# AT24-Timer.net
KiCad netlist of a schematic drawn in EAGLE
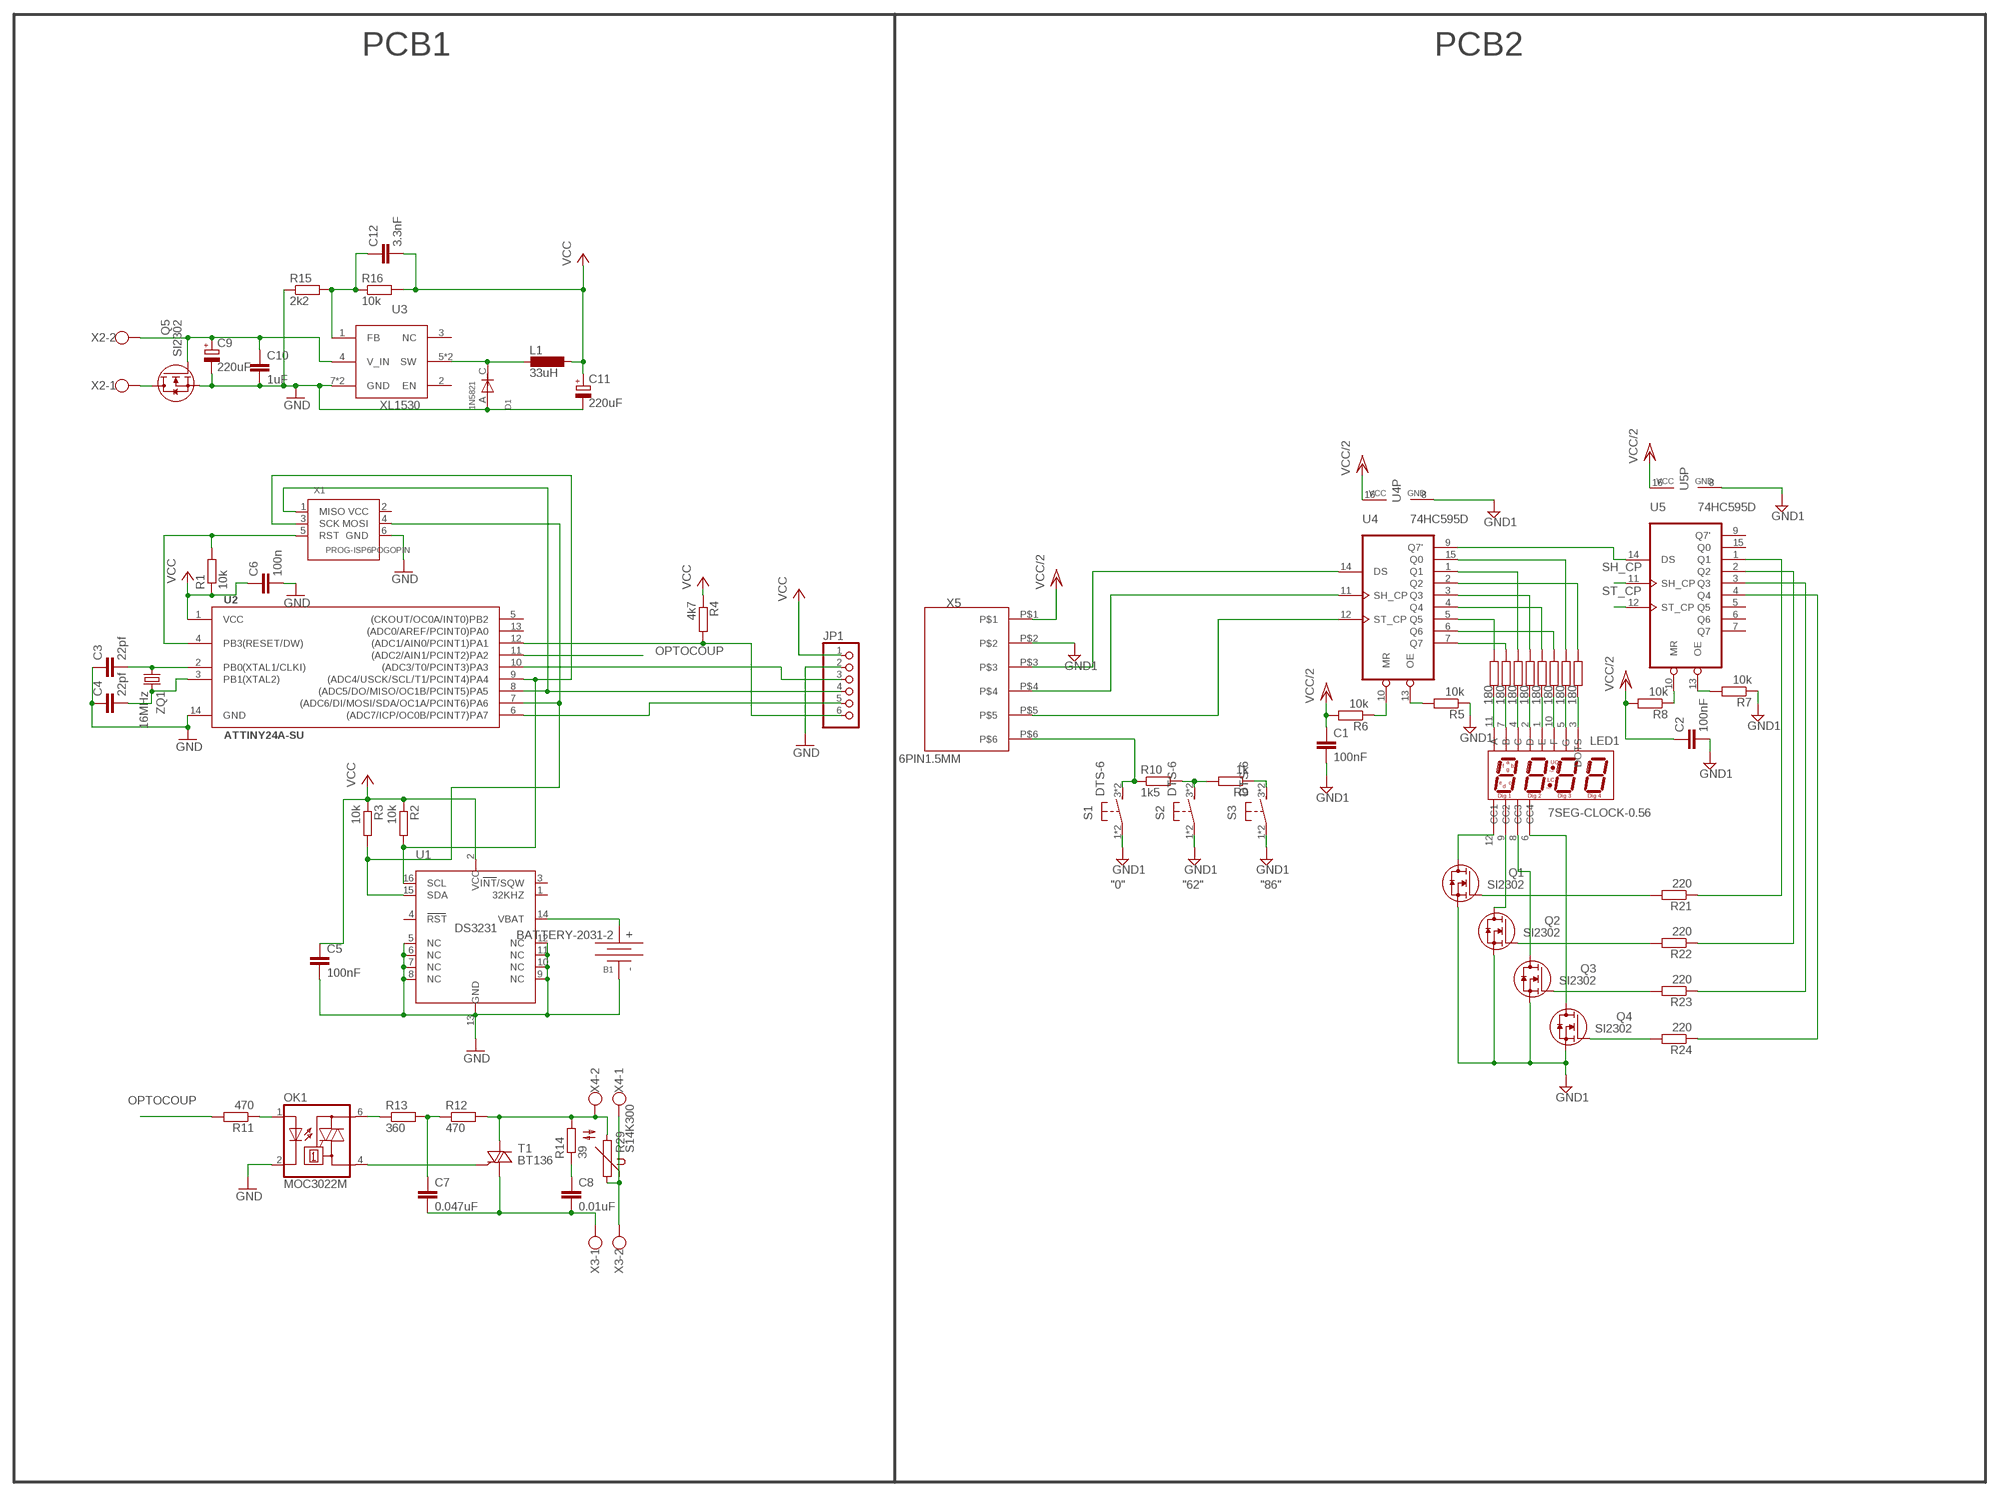
[diagram p0: schematic, sheet 1]

(export (version "E")
  (design (tool "Eeschema 10.0.6"))
  (components
    (comp (ref "B1")
      (value "BATTERY-2031-2")
      (footprint "eagle-import:BTH2032-2")
      (libsource (lib "eagle-import") (part "BATTERY-2031-2"))
    )
    (comp (ref "C1")
      (value "100nF")
      (footprint "eagle-import:C0603")
      (libsource (lib "eagle-import") (part "C-EUC0603"))
    )
    (comp (ref "C2")
      (value "100nF")
      (footprint "eagle-import:C0603")
      (libsource (lib "eagle-import") (part "C-EUC0603"))
    )
    (comp (ref "C3")
      (value "22pf")
      (footprint "eagle-import:C0603")
      (libsource (lib "eagle-import") (part "C-EUC0603"))
    )
    (comp (ref "C4")
      (value "22pf")
      (footprint "eagle-import:C0603")
      (libsource (lib "eagle-import") (part "C-EUC0603"))
    )
    (comp (ref "C5")
      (value "100nF")
      (footprint "eagle-import:C0603")
      (libsource (lib "eagle-import") (part "C-EUC0603"))
    )
    (comp (ref "C6")
      (value "100n")
      (footprint "eagle-import:C0603")
      (libsource (lib "eagle-import") (part "C-EUC0603"))
    )
    (comp (ref "C7")
      (value "0.047uF")
      (footprint "eagle-import:C150-054X183")
      (libsource (lib "eagle-import") (part "C-EU150-054X183"))
    )
    (comp (ref "C8")
      (value "0.01uF")
      (footprint "eagle-import:C102-043X133")
      (libsource (lib "eagle-import") (part "C-EU102-043X133"))
    )
    (comp (ref "C9")
      (value "220uF")
      (footprint "eagle-import:E2,5-6E")
      (libsource (lib "eagle-import") (part "CPOL-EUE2,5-6E"))
    )
    (comp (ref "C10")
      (value "1uF")
      (footprint "eagle-import:C0805")
      (libsource (lib "eagle-import") (part "C-EUC0805"))
    )
    (comp (ref "C11")
      (value "220uF")
      (footprint "eagle-import:E2,5-6E")
      (libsource (lib "eagle-import") (part "CPOL-EUE2,5-6E"))
    )
    (comp (ref "C12")
      (value "3.3nF")
      (footprint "eagle-import:C0805")
      (libsource (lib "eagle-import") (part "C-EUC0805"))
    )
    (comp (ref "D1")
      (value "1N5821")
      (footprint "eagle-import:DO214AC")
      (libsource (lib "eagle-import") (part "DIODESMD"))
    )
    (comp (ref "JP1")
      (value "PINHD-1X6")
      (footprint "eagle-import:1X06")
      (libsource (lib "eagle-import") (part "PINHD-1X6"))
    )
    (comp (ref "L1")
      (value "33uH")
      (footprint "eagle-import:L-SMD-D10")
      (libsource (lib "eagle-import") (part "L-SMD"))
    )
    (comp (ref "LED1")
      (value "7SEG-CLOCK-0.56")
      (footprint "eagle-import:7SEG_4DIG_0.56")
      (libsource (lib "eagle-import") (part "7SEG-CLOCK-0.56"))
    )
    (comp (ref "OK1")
      (value "MOC3022M")
      (footprint "eagle-import:DIL06")
      (fields (field (name "MF") "FAIRCHILD SEMICONDUCTOR") (field (name "MPN") "MOC3022-M"))
      (libsource (lib "eagle-import") (part "MOC30M22"))
    )
    (comp (ref "Q1")
      (value "SI2302")
      (footprint "eagle-import:SOT-23-GSD")
      (libsource (lib "eagle-import") (part "SI2302"))
    )
    (comp (ref "Q2")
      (value "SI2302")
      (footprint "eagle-import:SOT-23-GSD")
      (libsource (lib "eagle-import") (part "SI2302"))
    )
    (comp (ref "Q3")
      (value "SI2302")
      (footprint "eagle-import:SOT-23-GSD")
      (libsource (lib "eagle-import") (part "SI2302"))
    )
    (comp (ref "Q4")
      (value "SI2302")
      (footprint "eagle-import:SOT-23-GSD")
      (libsource (lib "eagle-import") (part "SI2302"))
    )
    (comp (ref "Q5")
      (value "SI2302")
      (footprint "eagle-import:SOT-23-GSD")
      (libsource (lib "eagle-import") (part "SI2302"))
    )
    (comp (ref "R1")
      (value "10k")
      (footprint "eagle-import:R0805")
      (libsource (lib "eagle-import") (part "R-EU_R0805"))
    )
    (comp (ref "R2")
      (value "10k")
      (footprint "eagle-import:R0805")
      (libsource (lib "eagle-import") (part "R-EU_R0805"))
    )
    (comp (ref "R3")
      (value "10k")
      (footprint "eagle-import:R0805")
      (libsource (lib "eagle-import") (part "R-EU_R0805"))
    )
    (comp (ref "R4")
      (value "4k7")
      (footprint "eagle-import:R0805")
      (libsource (lib "eagle-import") (part "R-EU_R0805"))
    )
    (comp (ref "R5")
      (value "10k")
      (footprint "eagle-import:R0805")
      (libsource (lib "eagle-import") (part "R-EU_R0805"))
    )
    (comp (ref "R6")
      (value "10k")
      (footprint "eagle-import:R0805")
      (libsource (lib "eagle-import") (part "R-EU_R0805"))
    )
    (comp (ref "R7")
      (value "10k")
      (footprint "eagle-import:R0805")
      (libsource (lib "eagle-import") (part "R-EU_R0805"))
    )
    (comp (ref "R8")
      (value "10k")
      (footprint "eagle-import:R0805")
      (libsource (lib "eagle-import") (part "R-EU_R0805"))
    )
    (comp (ref "R9")
      (value "1k")
      (footprint "eagle-import:R0805")
      (libsource (lib "eagle-import") (part "R-EU_R0805"))
    )
    (comp (ref "R10")
      (value "1k5")
      (footprint "eagle-import:R0805")
      (libsource (lib "eagle-import") (part "R-EU_R0805"))
    )
    (comp (ref "R11")
      (value "470")
      (footprint "eagle-import:R0805")
      (libsource (lib "eagle-import") (part "R-EU_R0805"))
    )
    (comp (ref "R12")
      (value "470")
      (footprint "eagle-import:0207_7")
      (libsource (lib "eagle-import") (part "R-EU_0207/7"))
    )
    (comp (ref "R13")
      (value "360")
      (footprint "eagle-import:0207_7")
      (libsource (lib "eagle-import") (part "R-EU_0207/7"))
    )
    (comp (ref "R14")
      (value "39")
      (footprint "eagle-import:0207_7")
      (libsource (lib "eagle-import") (part "R-EU_0207/7"))
    )
    (comp (ref "R15")
      (value "2k2")
      (footprint "eagle-import:R0603")
      (libsource (lib "eagle-import") (part "R-EU_R0603"))
    )
    (comp (ref "R16")
      (value "10k")
      (footprint "eagle-import:R0603")
      (libsource (lib "eagle-import") (part "R-EU_R0603"))
    )
    (comp (ref "R17")
      (value "180")
      (footprint "eagle-import:R0805")
      (libsource (lib "eagle-import") (part "R-EU_R0805"))
    )
    (comp (ref "R18")
      (value "180")
      (footprint "eagle-import:R0805")
      (libsource (lib "eagle-import") (part "R-EU_R0805"))
    )
    (comp (ref "R19")
      (value "180")
      (footprint "eagle-import:R0805")
      (libsource (lib "eagle-import") (part "R-EU_R0805"))
    )
    (comp (ref "R20")
      (value "180")
      (footprint "eagle-import:R0805")
      (libsource (lib "eagle-import") (part "R-EU_R0805"))
    )
    (comp (ref "R21")
      (value "220")
      (footprint "eagle-import:R0805")
      (libsource (lib "eagle-import") (part "R-EU_R0805"))
    )
    (comp (ref "R22")
      (value "220")
      (footprint "eagle-import:R0805")
      (libsource (lib "eagle-import") (part "R-EU_R0805"))
    )
    (comp (ref "R23")
      (value "220")
      (footprint "eagle-import:R0805")
      (libsource (lib "eagle-import") (part "R-EU_R0805"))
    )
    (comp (ref "R24")
      (value "220")
      (footprint "eagle-import:R0805")
      (libsource (lib "eagle-import") (part "R-EU_R0805"))
    )
    (comp (ref "R25")
      (value "180")
      (footprint "eagle-import:R0805")
      (libsource (lib "eagle-import") (part "R-EU_R0805"))
    )
    (comp (ref "R26")
      (value "180")
      (footprint "eagle-import:R0805")
      (libsource (lib "eagle-import") (part "R-EU_R0805"))
    )
    (comp (ref "R27")
      (value "180")
      (footprint "eagle-import:R0805")
      (libsource (lib "eagle-import") (part "R-EU_R0805"))
    )
    (comp (ref "R28")
      (value "180")
      (footprint "eagle-import:R0805")
      (libsource (lib "eagle-import") (part "R-EU_R0805"))
    )
    (comp (ref "R29")
      (value "S14K300")
      (footprint "eagle-import:S14K300")
      (libsource (lib "eagle-import") (part "S14K300"))
    )
    (comp (ref "S1")
      (value "DTS-6")
      (footprint "eagle-import:DTS-6")
      (libsource (lib "eagle-import") (part "DTS-6"))
    )
    (comp (ref "S2")
      (value "DTS-6")
      (footprint "eagle-import:DTS-6")
      (libsource (lib "eagle-import") (part "DTS-6"))
    )
    (comp (ref "S3")
      (value "DTS-6")
      (footprint "eagle-import:DTS-6")
      (libsource (lib "eagle-import") (part "DTS-6"))
    )
    (comp (ref "T1")
      (value "BT136")
      (footprint "eagle-import:TO220AB")
      (libsource (lib "eagle-import") (part "BT136"))
    )
    (comp (ref "U1")
      (value "DS3231")
      (footprint "eagle-import:SO16L")
      (libsource (lib "eagle-import") (part "DS3231"))
    )
    (comp (ref "U2")
      (value "ATTINY24A-SU")
      (footprint "eagle-import:SO14")
      (libsource (lib "eagle-import") (part "ATTINY24A-SU"))
    )
    (comp (ref "U3")
      (value "XL1530")
      (footprint "eagle-import:SOP08")
      (libsource (lib "eagle-import") (part "XL1530"))
    )
    (comp (ref "U4")
      (value "74HC595D")
      (footprint "eagle-import:SO16")
      (libsource (lib "eagle-import") (part "74595DHC"))
    )
    (comp (ref "U5")
      (value "74HC595D")
      (footprint "eagle-import:SO16")
      (libsource (lib "eagle-import") (part "74595DHC"))
    )
    (comp (ref "X1")
      (value "PROG-ISP6POGOPIN")
      (footprint "eagle-import:PROG_POGOPIN")
      (libsource (lib "eagle-import") (part "PROG-ISP6POGOPIN"))
    )
    (comp (ref "X2")
      (value "W237-102")
      (footprint "eagle-import:W237-102")
      (fields (field (name "MPN") "237-102"))
      (libsource (lib "eagle-import") (part "W237-102"))
    )
    (comp (ref "X3")
      (value "W237-102")
      (footprint "eagle-import:W237-102")
      (fields (field (name "MPN") "237-102"))
      (libsource (lib "eagle-import") (part "W237-102"))
    )
    (comp (ref "X4")
      (value "W237-102")
      (footprint "eagle-import:W237-102")
      (fields (field (name "MPN") "237-102"))
      (libsource (lib "eagle-import") (part "W237-102"))
    )
    (comp (ref "X5")
      (value "6PIN1.5MM")
      (footprint "eagle-import:6PIN_1.5MM")
      (libsource (lib "eagle-import") (part "6PIN1.5MM"))
    )
    (comp (ref "ZQ1")
      (value "16MHz")
      (footprint "eagle-import:HC49_S")
      (libsource (lib "eagle-import") (part "CRYSTALHC49S"))
    )
  )
  (nets
    (net (code "1") (name "/OPTOCOUP") (class "Default")
      (node (ref "R11") (pin "2") (pinfunction "2_2") (pintype "passive"))
      (node (ref "U2") (pin "11") (pinfunction "(ADC2/AIN1/PCINT2)PA2_11") (pintype "bidirectional"))
    )
    (net (code "2") (name "/SH_CP") (class "Default")
      (node (ref "U4") (pin "11") (pinfunction "SH_CP_11") (pintype "input"))
      (node (ref "U5") (pin "11") (pinfunction "SH_CP_11") (pintype "input"))
      (node (ref "X5") (pin "P$4") (pinfunction "P$4_P$4") (pintype "bidirectional"))
    )
    (net (code "3") (name "/ST_CP") (class "Default")
      (node (ref "U4") (pin "12") (pinfunction "ST_CP_12") (pintype "input"))
      (node (ref "U5") (pin "12") (pinfunction "ST_CP_12") (pintype "input"))
      (node (ref "X5") (pin "P$5") (pinfunction "P$5_P$5") (pintype "bidirectional"))
    )
    (net (code "4") (name "GND") (class "Default")
      (node (ref "B1") (pin "-") (pinfunction "-_-") (pintype "power_in"))
      (node (ref "C10") (pin "2") (pinfunction "2_2") (pintype "passive"))
      (node (ref "C11") (pin "-") (pinfunction "-_-") (pintype "passive"))
      (node (ref "C3") (pin "1") (pinfunction "1_1") (pintype "passive"))
      (node (ref "C4") (pin "1") (pinfunction "1_1") (pintype "passive"))
      (node (ref "C5") (pin "2") (pinfunction "2_2") (pintype "passive"))
      (node (ref "C6") (pin "2") (pinfunction "2_2") (pintype "passive"))
      (node (ref "C9") (pin "-") (pinfunction "-_-") (pintype "passive"))
      (node (ref "D1") (pin "A") (pinfunction "ANOD_A") (pintype "power_in"))
      (node (ref "JP1") (pin "2") (pinfunction "2_2") (pintype "passive"))
      (node (ref "OK1") (pin "2") (pinfunction "C_2") (pintype "passive"))
      (node (ref "Q5") (pin "S") (pinfunction "S_S") (pintype "passive"))
      (node (ref "R15") (pin "1") (pinfunction "1_1") (pintype "passive"))
      (node (ref "U1") (pin "10") (pinfunction "NC_10") (pintype "bidirectional"))
      (node (ref "U1") (pin "11") (pinfunction "NC_11") (pintype "bidirectional"))
      (node (ref "U1") (pin "12") (pinfunction "NC_12") (pintype "bidirectional"))
      (node (ref "U1") (pin "13") (pinfunction "GND_13") (pintype "power_in"))
      (node (ref "U1") (pin "5") (pinfunction "NC_5") (pintype "bidirectional"))
      (node (ref "U1") (pin "6") (pinfunction "NC_6") (pintype "bidirectional"))
      (node (ref "U1") (pin "7") (pinfunction "NC_7") (pintype "bidirectional"))
      (node (ref "U1") (pin "8") (pinfunction "NC_8") (pintype "bidirectional"))
      (node (ref "U1") (pin "9") (pinfunction "NC_9") (pintype "bidirectional"))
      (node (ref "U2") (pin "14") (pinfunction "GND_14") (pintype "power_in"))
      (node (ref "U3") (pin "7") (pinfunction "GND_7") (pintype "bidirectional"))
      (node (ref "U3") (pin "8") (pinfunction "GND_8") (pintype "bidirectional"))
      (node (ref "X1") (pin "6") (pinfunction "GND_6") (pintype "power_in"))
    )
    (net (code "5") (name "GND1") (class "Default")
      (node (ref "C1") (pin "2") (pinfunction "2_2") (pintype "passive"))
      (node (ref "C2") (pin "2") (pinfunction "2_2") (pintype "passive"))
      (node (ref "Q1") (pin "S") (pinfunction "S_S") (pintype "passive"))
      (node (ref "Q2") (pin "S") (pinfunction "S_S") (pintype "passive"))
      (node (ref "Q3") (pin "S") (pinfunction "S_S") (pintype "passive"))
      (node (ref "Q4") (pin "S") (pinfunction "S_S") (pintype "passive"))
      (node (ref "R5") (pin "1") (pinfunction "1_1") (pintype "passive"))
      (node (ref "R7") (pin "1") (pinfunction "1_1") (pintype "passive"))
      (node (ref "S1") (pin "1") (pinfunction "1_1") (pintype "passive"))
      (node (ref "S1") (pin "2") (pinfunction "1_2") (pintype "passive"))
      (node (ref "S2") (pin "1") (pinfunction "1_1") (pintype "passive"))
      (node (ref "S2") (pin "2") (pinfunction "1_2") (pintype "passive"))
      (node (ref "S3") (pin "1") (pinfunction "1_1") (pintype "passive"))
      (node (ref "S3") (pin "2") (pinfunction "1_2") (pintype "passive"))
      (node (ref "U4") (pin "8") (pinfunction "GND_8") (pintype "power_in"))
      (node (ref "U5") (pin "8") (pinfunction "GND_8") (pintype "power_in"))
      (node (ref "X5") (pin "P$2") (pinfunction "P$2_P$2") (pintype "bidirectional"))
    )
    (net (code "6") (name "Net-(C7-Pad1)") (class "Default")
      (node (ref "C7") (pin "1") (pinfunction "1_1") (pintype "passive"))
      (node (ref "R12") (pin "1") (pinfunction "1_1") (pintype "passive"))
      (node (ref "R13") (pin "2") (pinfunction "2_2") (pintype "passive"))
    )
    (net (code "7") (name "Net-(C8-Pad1)") (class "Default")
      (node (ref "C8") (pin "1") (pinfunction "1_1") (pintype "passive"))
      (node (ref "R14") (pin "1") (pinfunction "1_1") (pintype "passive"))
    )
    (net (code "8") (name "Net-(D1-KATOD)") (class "Default")
      (node (ref "D1") (pin "C") (pinfunction "KATOD_C") (pintype "power_in"))
      (node (ref "L1") (pin "P$2") (pinfunction "2_P$2") (pintype "passive"))
      (node (ref "U3") (pin "5") (pinfunction "SW_5") (pintype "bidirectional"))
      (node (ref "U3") (pin "6") (pinfunction "SW_6") (pintype "bidirectional"))
    )
    (net (code "9") (name "Net-(LED1-A)") (class "Default")
      (node (ref "LED1") (pin "11") (pinfunction "A_11") (pintype "input"))
      (node (ref "R17") (pin "2") (pinfunction "2_2") (pintype "passive"))
    )
    (net (code "10") (name "Net-(LED1-B)") (class "Default")
      (node (ref "LED1") (pin "7") (pinfunction "B_7") (pintype "input"))
      (node (ref "R18") (pin "2") (pinfunction "2_2") (pintype "passive"))
    )
    (net (code "11") (name "Net-(LED1-C)") (class "Default")
      (node (ref "LED1") (pin "4") (pinfunction "C_4") (pintype "input"))
      (node (ref "R19") (pin "2") (pinfunction "2_2") (pintype "passive"))
    )
    (net (code "12") (name "Net-(LED1-CC1)") (class "Default")
      (node (ref "LED1") (pin "12") (pinfunction "CC1_12") (pintype "input"))
      (node (ref "Q1") (pin "D") (pinfunction "D_D") (pintype "passive"))
    )
    (net (code "13") (name "Net-(LED1-CC2)") (class "Default")
      (node (ref "LED1") (pin "9") (pinfunction "CC2_9") (pintype "input"))
      (node (ref "Q2") (pin "D") (pinfunction "D_D") (pintype "passive"))
    )
    (net (code "14") (name "Net-(LED1-CC3)") (class "Default")
      (node (ref "LED1") (pin "8") (pinfunction "CC3_8") (pintype "input"))
      (node (ref "Q3") (pin "D") (pinfunction "D_D") (pintype "passive"))
    )
    (net (code "15") (name "Net-(LED1-CC4)") (class "Default")
      (node (ref "LED1") (pin "6") (pinfunction "CC4_6") (pintype "input"))
      (node (ref "Q4") (pin "D") (pinfunction "D_D") (pintype "passive"))
    )
    (net (code "16") (name "Net-(LED1-D)") (class "Default")
      (node (ref "LED1") (pin "2") (pinfunction "D_2") (pintype "input"))
      (node (ref "R20") (pin "2") (pinfunction "2_2") (pintype "passive"))
    )
    (net (code "17") (name "Net-(LED1-DOTS)") (class "Default")
      (node (ref "LED1") (pin "3") (pinfunction "DOTS_3") (pintype "input"))
      (node (ref "R28") (pin "2") (pinfunction "2_2") (pintype "passive"))
    )
    (net (code "18") (name "Net-(LED1-E)") (class "Default")
      (node (ref "LED1") (pin "1") (pinfunction "E_1") (pintype "input"))
      (node (ref "R25") (pin "2") (pinfunction "2_2") (pintype "passive"))
    )
    (net (code "19") (name "Net-(LED1-F)") (class "Default")
      (node (ref "LED1") (pin "10") (pinfunction "F_10") (pintype "input"))
      (node (ref "R26") (pin "2") (pinfunction "2_2") (pintype "passive"))
    )
    (net (code "20") (name "Net-(LED1-G)") (class "Default")
      (node (ref "LED1") (pin "5") (pinfunction "G_5") (pintype "input"))
      (node (ref "R27") (pin "2") (pinfunction "2_2") (pintype "passive"))
    )
    (net (code "21") (name "Net-(OK1-A)") (class "Default")
      (node (ref "OK1") (pin "1") (pinfunction "A_1") (pintype "passive"))
      (node (ref "R11") (pin "1") (pinfunction "1_1") (pintype "passive"))
    )
    (net (code "22") (name "Net-(OK1-A1)") (class "Default")
      (node (ref "OK1") (pin "4") (pinfunction "A1_4") (pintype "passive"))
      (node (ref "T1") (pin "3") (pinfunction "G_3") (pintype "passive"))
    )
    (net (code "23") (name "Net-(OK1-A2)") (class "Default")
      (node (ref "OK1") (pin "6") (pinfunction "A2_6") (pintype "passive"))
      (node (ref "R13") (pin "1") (pinfunction "1_1") (pintype "passive"))
    )
    (net (code "24") (name "Net-(Q1-PadG)") (class "Default")
      (node (ref "Q1") (pin "G") (pinfunction "G_G") (pintype "passive"))
      (node (ref "R21") (pin "2") (pinfunction "2_2") (pintype "passive"))
    )
    (net (code "25") (name "Net-(Q2-PadG)") (class "Default")
      (node (ref "Q2") (pin "G") (pinfunction "G_G") (pintype "passive"))
      (node (ref "R22") (pin "2") (pinfunction "2_2") (pintype "passive"))
    )
    (net (code "26") (name "Net-(Q3-PadG)") (class "Default")
      (node (ref "Q3") (pin "G") (pinfunction "G_G") (pintype "passive"))
      (node (ref "R23") (pin "2") (pinfunction "2_2") (pintype "passive"))
    )
    (net (code "27") (name "Net-(Q4-PadG)") (class "Default")
      (node (ref "Q4") (pin "G") (pinfunction "G_G") (pintype "passive"))
      (node (ref "R24") (pin "2") (pinfunction "2_2") (pintype "passive"))
    )
    (net (code "28") (name "Net-(R9-Pad1)") (class "Default")
      (node (ref "R9") (pin "1") (pinfunction "1_1") (pintype "passive"))
      (node (ref "S3") (pin "3") (pinfunction "2_3") (pintype "passive"))
      (node (ref "S3") (pin "4") (pinfunction "2_4") (pintype "passive"))
    )
    (net (code "29") (name "Net-(R10-Pad1)") (class "Default")
      (node (ref "R10") (pin "1") (pinfunction "1_1") (pintype "passive"))
      (node (ref "S1") (pin "3") (pinfunction "2_3") (pintype "passive"))
      (node (ref "S1") (pin "4") (pinfunction "2_4") (pintype "passive"))
      (node (ref "X5") (pin "P$6") (pinfunction "P$6_P$6") (pintype "bidirectional"))
    )
    (net (code "30") (name "Net-(R10-Pad2)") (class "Default")
      (node (ref "R10") (pin "2") (pinfunction "2_2") (pintype "passive"))
      (node (ref "R9") (pin "2") (pinfunction "2_2") (pintype "passive"))
      (node (ref "S2") (pin "3") (pinfunction "2_3") (pintype "passive"))
      (node (ref "S2") (pin "4") (pinfunction "2_4") (pintype "passive"))
    )
    (net (code "31") (name "Net-(T1-A1)") (class "Default")
      (node (ref "C7") (pin "2") (pinfunction "2_2") (pintype "passive"))
      (node (ref "C8") (pin "2") (pinfunction "2_2") (pintype "passive"))
      (node (ref "T1") (pin "1") (pinfunction "A1_1") (pintype "passive"))
      (node (ref "X3") (pin "1") (pinfunction "KL_1") (pintype "passive"))
    )
    (net (code "32") (name "Net-(T1-A2)") (class "Default")
      (node (ref "R12") (pin "2") (pinfunction "2_2") (pintype "passive"))
      (node (ref "R14") (pin "2") (pinfunction "2_2") (pintype "passive"))
      (node (ref "R29") (pin "2") (pinfunction "2_2") (pintype "passive"))
      (node (ref "T1") (pin "2") (pinfunction "A2_2") (pintype "passive"))
      (node (ref "X4") (pin "2") (pinfunction "KL_2") (pintype "passive"))
    )
    (net (code "33") (name "Net-(U1-SCL)") (class "Default")
      (node (ref "R2") (pin "2") (pinfunction "2_2") (pintype "passive"))
      (node (ref "U1") (pin "16") (pinfunction "SCL_16") (pintype "bidirectional"))
      (node (ref "U2") (pin "9") (pinfunction "(ADC4/USCK/SCL/T1/PCINT4)PA4_9") (pintype "bidirectional"))
      (node (ref "X1") (pin "3") (pinfunction "SCK_3") (pintype "bidirectional"))
    )
    (net (code "34") (name "Net-(U1-SDA)") (class "Default")
      (node (ref "R3") (pin "2") (pinfunction "2_2") (pintype "passive"))
      (node (ref "U1") (pin "15") (pinfunction "SDA_15") (pintype "bidirectional"))
      (node (ref "U2") (pin "7") (pinfunction "(ADC6/DI/MOSI/SDA/OC1A/PCINT6)PA6_7") (pintype "bidirectional"))
      (node (ref "X1") (pin "4") (pinfunction "MOSI_4") (pintype "bidirectional"))
    )
    (net (code "35") (name "Net-(U1-VBAT)") (class "Default")
      (node (ref "B1") (pin "+") (pinfunction "+_+") (pintype "power_in"))
      (node (ref "U1") (pin "14") (pinfunction "VBAT_14") (pintype "bidirectional"))
    )
    (net (code "36") (name "Net-(U2-(ADC1{slash}AIN0{slash}PCINT1)PA1)") (class "Default")
      (node (ref "JP1") (pin "6") (pinfunction "6_6") (pintype "passive"))
      (node (ref "R4") (pin "2") (pinfunction "2_2") (pintype "passive"))
      (node (ref "U2") (pin "12") (pinfunction "(ADC1/AIN0/PCINT1)PA1_12") (pintype "bidirectional"))
    )
    (net (code "37") (name "Net-(U2-(ADC3{slash}T0{slash}PCINT3)PA3)") (class "Default")
      (node (ref "JP1") (pin "3") (pinfunction "3_3") (pintype "passive"))
      (node (ref "U2") (pin "10") (pinfunction "(ADC3/T0/PCINT3)PA3_10") (pintype "bidirectional"))
    )
    (net (code "38") (name "Net-(U2-(ADC5{slash}DO{slash}MISO{slash}OC1B{slash}PCINT5)PA5)") (class "Default")
      (node (ref "JP1") (pin "4") (pinfunction "4_4") (pintype "passive"))
      (node (ref "U2") (pin "8") (pinfunction "(ADC5/DO/MISO/OC1B/PCINT5)PA5_8") (pintype "bidirectional"))
      (node (ref "X1") (pin "1") (pinfunction "MISO_1") (pintype "bidirectional"))
    )
    (net (code "39") (name "Net-(U2-(ADC7{slash}ICP{slash}OC0B{slash}PCINT7)PA7)") (class "Default")
      (node (ref "JP1") (pin "5") (pinfunction "5_5") (pintype "passive"))
      (node (ref "U2") (pin "6") (pinfunction "(ADC7/ICP/OC0B/PCINT7)PA7_6") (pintype "bidirectional"))
    )
    (net (code "40") (name "Net-(U2-PB0(XTAL1{slash}CLKI))") (class "Default")
      (node (ref "C3") (pin "2") (pinfunction "2_2") (pintype "passive"))
      (node (ref "U2") (pin "2") (pinfunction "PB0(XTAL1/CLKI)_2") (pintype "bidirectional"))
      (node (ref "ZQ1") (pin "1") (pinfunction "1_1") (pintype "passive"))
    )
    (net (code "41") (name "Net-(U2-PB1(XTAL2))") (class "Default")
      (node (ref "C4") (pin "2") (pinfunction "2_2") (pintype "passive"))
      (node (ref "U2") (pin "3") (pinfunction "PB1(XTAL2)_3") (pintype "bidirectional"))
      (node (ref "ZQ1") (pin "2") (pinfunction "2_2") (pintype "passive"))
    )
    (net (code "42") (name "Net-(U2-PB3(RESET{slash}DW))") (class "Default")
      (node (ref "R1") (pin "2") (pinfunction "2_2") (pintype "passive"))
      (node (ref "U2") (pin "4") (pinfunction "PB3(RESET/DW)_4") (pintype "bidirectional"))
      (node (ref "X1") (pin "5") (pinfunction "RST_5") (pintype "bidirectional"))
    )
    (net (code "43") (name "Net-(U3-FB)") (class "Default")
      (node (ref "C12") (pin "1") (pinfunction "1_1") (pintype "passive"))
      (node (ref "R15") (pin "2") (pinfunction "2_2") (pintype "passive"))
      (node (ref "R16") (pin "1") (pinfunction "1_1") (pintype "passive"))
      (node (ref "U3") (pin "1") (pinfunction "FB_1") (pintype "bidirectional"))
    )
    (net (code "44") (name "Net-(U3-V_IN)") (class "Default")
      (node (ref "C10") (pin "1") (pinfunction "1_1") (pintype "passive"))
      (node (ref "C9") (pin "+") (pinfunction "+_+") (pintype "passive"))
      (node (ref "Q5") (pin "G") (pinfunction "G_G") (pintype "passive"))
      (node (ref "U3") (pin "4") (pinfunction "V_IN_4") (pintype "bidirectional"))
      (node (ref "X2") (pin "2") (pinfunction "KL_2") (pintype "passive"))
    )
    (net (code "45") (name "Net-(U4A-DS)") (class "Default")
      (node (ref "U4") (pin "14") (pinfunction "DS_14") (pintype "input"))
      (node (ref "X5") (pin "P$3") (pinfunction "P$3_P$3") (pintype "bidirectional"))
    )
    (net (code "46") (name "Net-(U4A-MR)") (class "Default")
      (node (ref "R6") (pin "1") (pinfunction "1_1") (pintype "passive"))
      (node (ref "U4") (pin "10") (pinfunction "MR_10") (pintype "input"))
    )
    (net (code "47") (name "Net-(U4A-OE)") (class "Default")
      (node (ref "R5") (pin "2") (pinfunction "2_2") (pintype "passive"))
      (node (ref "U4") (pin "13") (pinfunction "OE_13") (pintype "input"))
    )
    (net (code "48") (name "Net-(U4A-Q0)") (class "Default")
      (node (ref "R27") (pin "1") (pinfunction "1_1") (pintype "passive"))
      (node (ref "U4") (pin "15") (pinfunction "Q0_15") (pintype "output"))
    )
    (net (code "49") (name "Net-(U4A-Q1)") (class "Default")
      (node (ref "R19") (pin "1") (pinfunction "1_1") (pintype "passive"))
      (node (ref "U4") (pin "1") (pinfunction "Q1_1") (pintype "output"))
    )
    (net (code "50") (name "Net-(U4A-Q2)") (class "Default")
      (node (ref "R28") (pin "1") (pinfunction "1_1") (pintype "passive"))
      (node (ref "U4") (pin "2") (pinfunction "Q2_2") (pintype "output"))
    )
    (net (code "51") (name "Net-(U4A-Q3)") (class "Default")
      (node (ref "R20") (pin "1") (pinfunction "1_1") (pintype "passive"))
      (node (ref "U4") (pin "3") (pinfunction "Q3_3") (pintype "output"))
    )
    (net (code "52") (name "Net-(U4A-Q4)") (class "Default")
      (node (ref "R25") (pin "1") (pinfunction "1_1") (pintype "passive"))
      (node (ref "U4") (pin "4") (pinfunction "Q4_4") (pintype "output"))
    )
    (net (code "53") (name "Net-(U4A-Q5)") (class "Default")
      (node (ref "R17") (pin "1") (pinfunction "1_1") (pintype "passive"))
      (node (ref "U4") (pin "5") (pinfunction "Q5_5") (pintype "output"))
    )
    (net (code "54") (name "Net-(U4A-Q6)") (class "Default")
      (node (ref "R26") (pin "1") (pinfunction "1_1") (pintype "passive"))
      (node (ref "U4") (pin "6") (pinfunction "Q6_6") (pintype "output"))
    )
    (net (code "55") (name "Net-(U4A-Q7')") (class "Default")
      (node (ref "U4") (pin "9") (pinfunction "Q7'_9") (pintype "output"))
      (node (ref "U5") (pin "14") (pinfunction "DS_14") (pintype "input"))
    )
    (net (code "56") (name "Net-(U4A-Q7)") (class "Default")
      (node (ref "R18") (pin "1") (pinfunction "1_1") (pintype "passive"))
      (node (ref "U4") (pin "7") (pinfunction "Q7_7") (pintype "output"))
    )
    (net (code "57") (name "Net-(U5A-MR)") (class "Default")
      (node (ref "R8") (pin "1") (pinfunction "1_1") (pintype "passive"))
      (node (ref "U5") (pin "10") (pinfunction "MR_10") (pintype "input"))
    )
    (net (code "58") (name "Net-(U5A-OE)") (class "Default")
      (node (ref "R7") (pin "2") (pinfunction "2_2") (pintype "passive"))
      (node (ref "U5") (pin "13") (pinfunction "OE_13") (pintype "input"))
    )
    (net (code "59") (name "Net-(U5A-Q1)") (class "Default")
      (node (ref "R21") (pin "1") (pinfunction "1_1") (pintype "passive"))
      (node (ref "U5") (pin "1") (pinfunction "Q1_1") (pintype "output"))
    )
    (net (code "60") (name "Net-(U5A-Q2)") (class "Default")
      (node (ref "R22") (pin "1") (pinfunction "1_1") (pintype "passive"))
      (node (ref "U5") (pin "2") (pinfunction "Q2_2") (pintype "output"))
    )
    (net (code "61") (name "Net-(U5A-Q3)") (class "Default")
      (node (ref "R23") (pin "1") (pinfunction "1_1") (pintype "passive"))
      (node (ref "U5") (pin "3") (pinfunction "Q3_3") (pintype "output"))
    )
    (net (code "62") (name "Net-(U5A-Q4)") (class "Default")
      (node (ref "R24") (pin "1") (pinfunction "1_1") (pintype "passive"))
      (node (ref "U5") (pin "4") (pinfunction "Q4_4") (pintype "output"))
    )
    (net (code "63") (name "Net-(X2A-KL)") (class "Default")
      (node (ref "Q5") (pin "D") (pinfunction "D_D") (pintype "passive"))
      (node (ref "X2") (pin "1") (pinfunction "KL_1") (pintype "passive"))
    )
    (net (code "64") (name "Net-(X3B-KL)") (class "Default")
      (node (ref "R29") (pin "1") (pinfunction "1_1") (pintype "passive"))
      (node (ref "X3") (pin "2") (pinfunction "KL_2") (pintype "passive"))
      (node (ref "X4") (pin "1") (pinfunction "KL_1") (pintype "passive"))
    )
    (net (code "65") (name "VCC") (class "Default")
      (node (ref "C11") (pin "+") (pinfunction "+_+") (pintype "passive"))
      (node (ref "C12") (pin "2") (pinfunction "2_2") (pintype "passive"))
      (node (ref "C5") (pin "1") (pinfunction "1_1") (pintype "passive"))
      (node (ref "C6") (pin "1") (pinfunction "1_1") (pintype "passive"))
      (node (ref "JP1") (pin "1") (pinfunction "1_1") (pintype "passive"))
      (node (ref "L1") (pin "P$1") (pinfunction "1_P$1") (pintype "passive"))
      (node (ref "R1") (pin "1") (pinfunction "1_1") (pintype "passive"))
      (node (ref "R16") (pin "2") (pinfunction "2_2") (pintype "passive"))
      (node (ref "R2") (pin "1") (pinfunction "1_1") (pintype "passive"))
      (node (ref "R3") (pin "1") (pinfunction "1_1") (pintype "passive"))
      (node (ref "R4") (pin "1") (pinfunction "1_1") (pintype "passive"))
      (node (ref "U1") (pin "2") (pinfunction "VCC_2") (pintype "power_in"))
      (node (ref "U2") (pin "1") (pinfunction "VCC_1") (pintype "power_in"))
    )
    (net (code "66") (name "VCC{slash}2") (class "Default")
      (node (ref "C1") (pin "1") (pinfunction "1_1") (pintype "passive"))
      (node (ref "C2") (pin "1") (pinfunction "1_1") (pintype "passive"))
      (node (ref "R6") (pin "2") (pinfunction "2_2") (pintype "passive"))
      (node (ref "R8") (pin "2") (pinfunction "2_2") (pintype "passive"))
      (node (ref "U4") (pin "16") (pinfunction "VCC_16") (pintype "power_in"))
      (node (ref "U5") (pin "16") (pinfunction "VCC_16") (pintype "power_in"))
      (node (ref "X5") (pin "P$1") (pinfunction "P$1_P$1") (pintype "bidirectional"))
    )
    (net (code "67") (name "unconnected-(U1-32KHZ-Pad1)") (class "Default")
      (node (ref "U1") (pin "1") (pinfunction "32KHZ_1") (pintype "bidirectional"))
    )
    (net (code "68") (name "unconnected-(U1-INT{slash}SQW-Pad3)") (class "Default")
      (node (ref "U1") (pin "3") (pinfunction "INT/SQW_3") (pintype "bidirectional"))
    )
    (net (code "69") (name "unconnected-(U1-RST-Pad4)") (class "Default")
      (node (ref "U1") (pin "4") (pinfunction "RST_4") (pintype "bidirectional"))
    )
    (net (code "70") (name "unconnected-(U2-(ADC0{slash}AREF{slash}PCINT0)PA0-Pad13)") (class "Default")
      (node (ref "U2") (pin "13") (pinfunction "(ADC0/AREF/PCINT0)PA0_13") (pintype "bidirectional"))
    )
    (net (code "71") (name "unconnected-(U2-(CKOUT{slash}OC0A{slash}INT0)PB2-Pad5)") (class "Default")
      (node (ref "U2") (pin "5") (pinfunction "(CKOUT/OC0A/INT0)PB2_5") (pintype "bidirectional"))
    )
    (net (code "72") (name "unconnected-(U3-EN-Pad2)") (class "Default")
      (node (ref "U3") (pin "2") (pinfunction "EN_2") (pintype "bidirectional"))
    )
    (net (code "73") (name "unconnected-(U3-NC-Pad3)") (class "Default")
      (node (ref "U3") (pin "3") (pinfunction "NC_3") (pintype "bidirectional"))
    )
    (net (code "74") (name "unconnected-(U5A-Q0-Pad15)") (class "Default")
      (node (ref "U5") (pin "15") (pinfunction "Q0_15") (pintype "output"))
    )
    (net (code "75") (name "unconnected-(U5A-Q5-Pad5)") (class "Default")
      (node (ref "U5") (pin "5") (pinfunction "Q5_5") (pintype "output"))
    )
    (net (code "76") (name "unconnected-(U5A-Q6-Pad6)") (class "Default")
      (node (ref "U5") (pin "6") (pinfunction "Q6_6") (pintype "output"))
    )
    (net (code "77") (name "unconnected-(U5A-Q7'-Pad9)") (class "Default")
      (node (ref "U5") (pin "9") (pinfunction "Q7'_9") (pintype "output"))
    )
    (net (code "78") (name "unconnected-(U5A-Q7-Pad7)") (class "Default")
      (node (ref "U5") (pin "7") (pinfunction "Q7_7") (pintype "output"))
    )
    (net (code "79") (name "unconnected-(X1-VCC-Pad2)") (class "Default")
      (node (ref "X1") (pin "2") (pinfunction "VCC_2") (pintype "bidirectional"))
    )
  )
)
